# 12_V_Supply.net
KiCad netlist of a schematic drawn in EAGLE
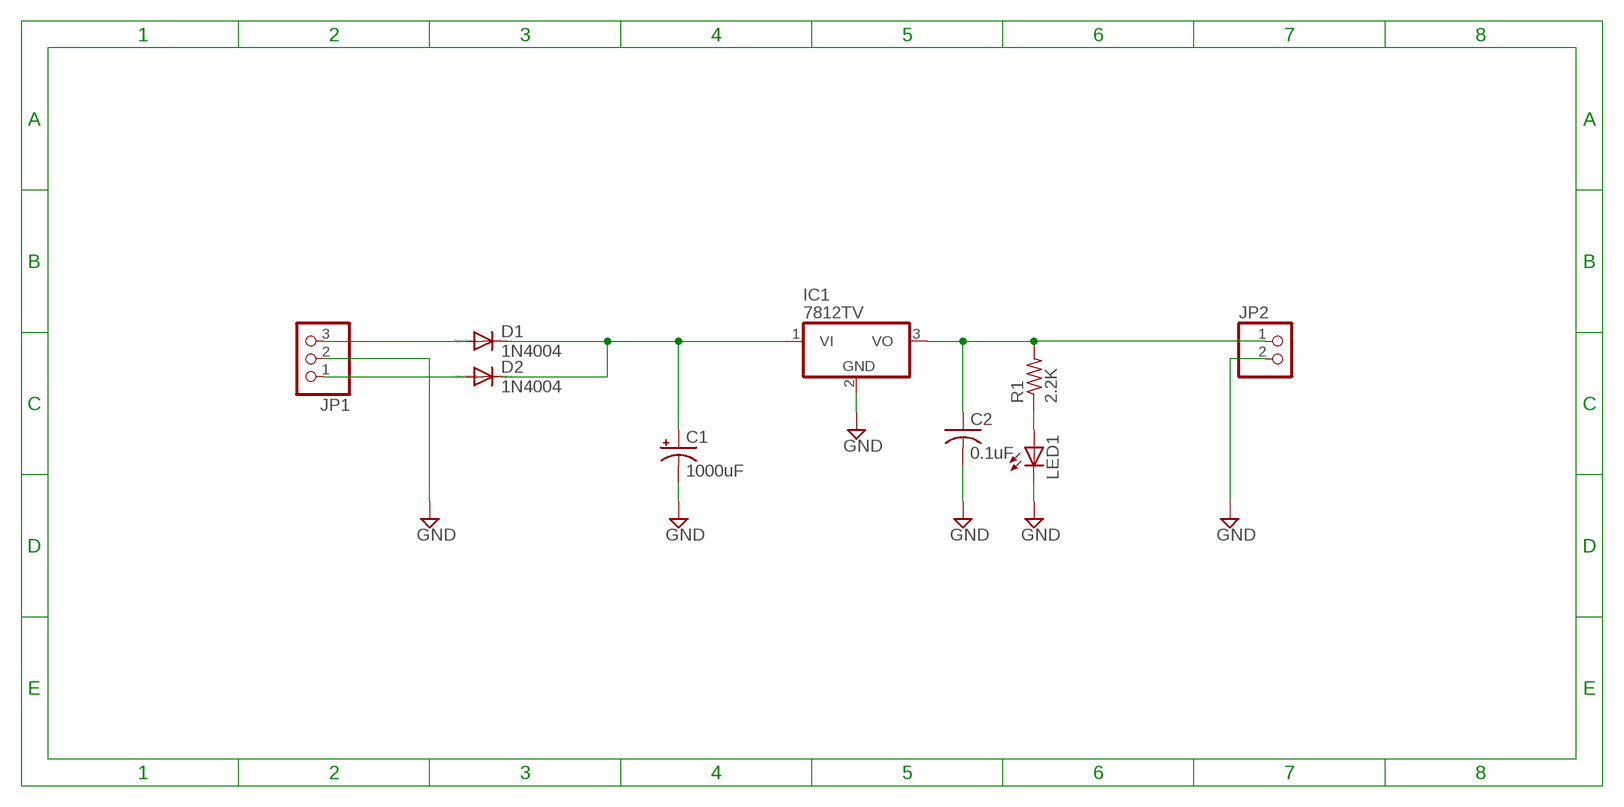
[diagram p0: schematic, sheet 1]

(export (version "E")
  (design (tool "Eeschema 10.0.6"))
  (components
    (comp (ref "C1")
      (value "1000uF")
      (footprint "eagle-import:E5-10,5")
      (libsource (lib "eagle-import") (part "CPOL-USE5-10.5"))
    )
    (comp (ref "C2")
      (value "0.1uF")
      (footprint "eagle-import:C050-025X075")
      (libsource (lib "eagle-import") (part "C-US050-025X075"))
    )
    (comp (ref "D1")
      (value "1N4004")
      (footprint "eagle-import:DO41-10")
      (libsource (lib "eagle-import") (part "1N4004"))
    )
    (comp (ref "D2")
      (value "1N4004")
      (footprint "eagle-import:DO41-10")
      (libsource (lib "eagle-import") (part "1N4004"))
    )
    (comp (ref "IC1")
      (value "7812TV")
      (footprint "eagle-import:TO220V")
      (libsource (lib "eagle-import") (part "78TV12"))
    )
    (comp (ref "JP1")
      (value "PINHD-1X3")
      (footprint "eagle-import:1X03")
      (libsource (lib "eagle-import") (part "PINHD-1X3"))
    )
    (comp (ref "JP2")
      (value "PINHD-1X2")
      (footprint "eagle-import:1X02")
      (libsource (lib "eagle-import") (part "PINHD-1X2"))
    )
    (comp (ref "LED1")
      (value "LED5MM")
      (footprint "eagle-import:LED5MM")
      (libsource (lib "eagle-import") (part "LED5MM"))
    )
    (comp (ref "R1")
      (value "2.2K")
      (footprint "eagle-import:0207_10")
      (libsource (lib "eagle-import") (part "R-US_0207/10"))
    )
  )
  (nets
    (net (code "1") (name "GND") (class "Default")
      (node (ref "C1") (pin "-") (pinfunction "-_-") (pintype "passive"))
      (node (ref "C2") (pin "2") (pinfunction "2_2") (pintype "passive"))
      (node (ref "IC1") (pin "2") (pinfunction "GND_2") (pintype "passive"))
      (node (ref "JP1") (pin "2") (pinfunction "2_2") (pintype "passive"))
      (node (ref "JP2") (pin "2") (pinfunction "2_2") (pintype "passive"))
      (node (ref "LED1") (pin "K") (pinfunction "C_K") (pintype "passive"))
    )
    (net (code "2") (name "Net-(D1-PadA)") (class "Default")
      (node (ref "D1") (pin "A") (pinfunction "A_A") (pintype "passive"))
      (node (ref "JP1") (pin "3") (pinfunction "3_3") (pintype "passive"))
    )
    (net (code "3") (name "Net-(D2-PadA)") (class "Default")
      (node (ref "D2") (pin "A") (pinfunction "A_A") (pintype "passive"))
      (node (ref "JP1") (pin "1") (pinfunction "1_1") (pintype "passive"))
    )
    (net (code "4") (name "Net-(IC1-VI)") (class "Default")
      (node (ref "C1") (pin "+") (pinfunction "+_+") (pintype "passive"))
      (node (ref "D1") (pin "C") (pinfunction "C_C") (pintype "passive"))
      (node (ref "D2") (pin "C") (pinfunction "C_C") (pintype "passive"))
      (node (ref "IC1") (pin "1") (pinfunction "VI_1") (pintype "input"))
    )
    (net (code "5") (name "Net-(IC1-VO)") (class "Default")
      (node (ref "C2") (pin "1") (pinfunction "1_1") (pintype "passive"))
      (node (ref "IC1") (pin "3") (pinfunction "VO_3") (pintype "passive"))
      (node (ref "JP2") (pin "1") (pinfunction "1_1") (pintype "passive"))
      (node (ref "R1") (pin "2") (pinfunction "2_2") (pintype "passive"))
    )
    (net (code "6") (name "Net-(LED1-PadA)") (class "Default")
      (node (ref "LED1") (pin "A") (pinfunction "A_A") (pintype "passive"))
      (node (ref "R1") (pin "1") (pinfunction "1_1") (pintype "passive"))
    )
  )
)
